# A01_POWER_MCU.net
KiCad netlist of a schematic drawn in Altium Designer
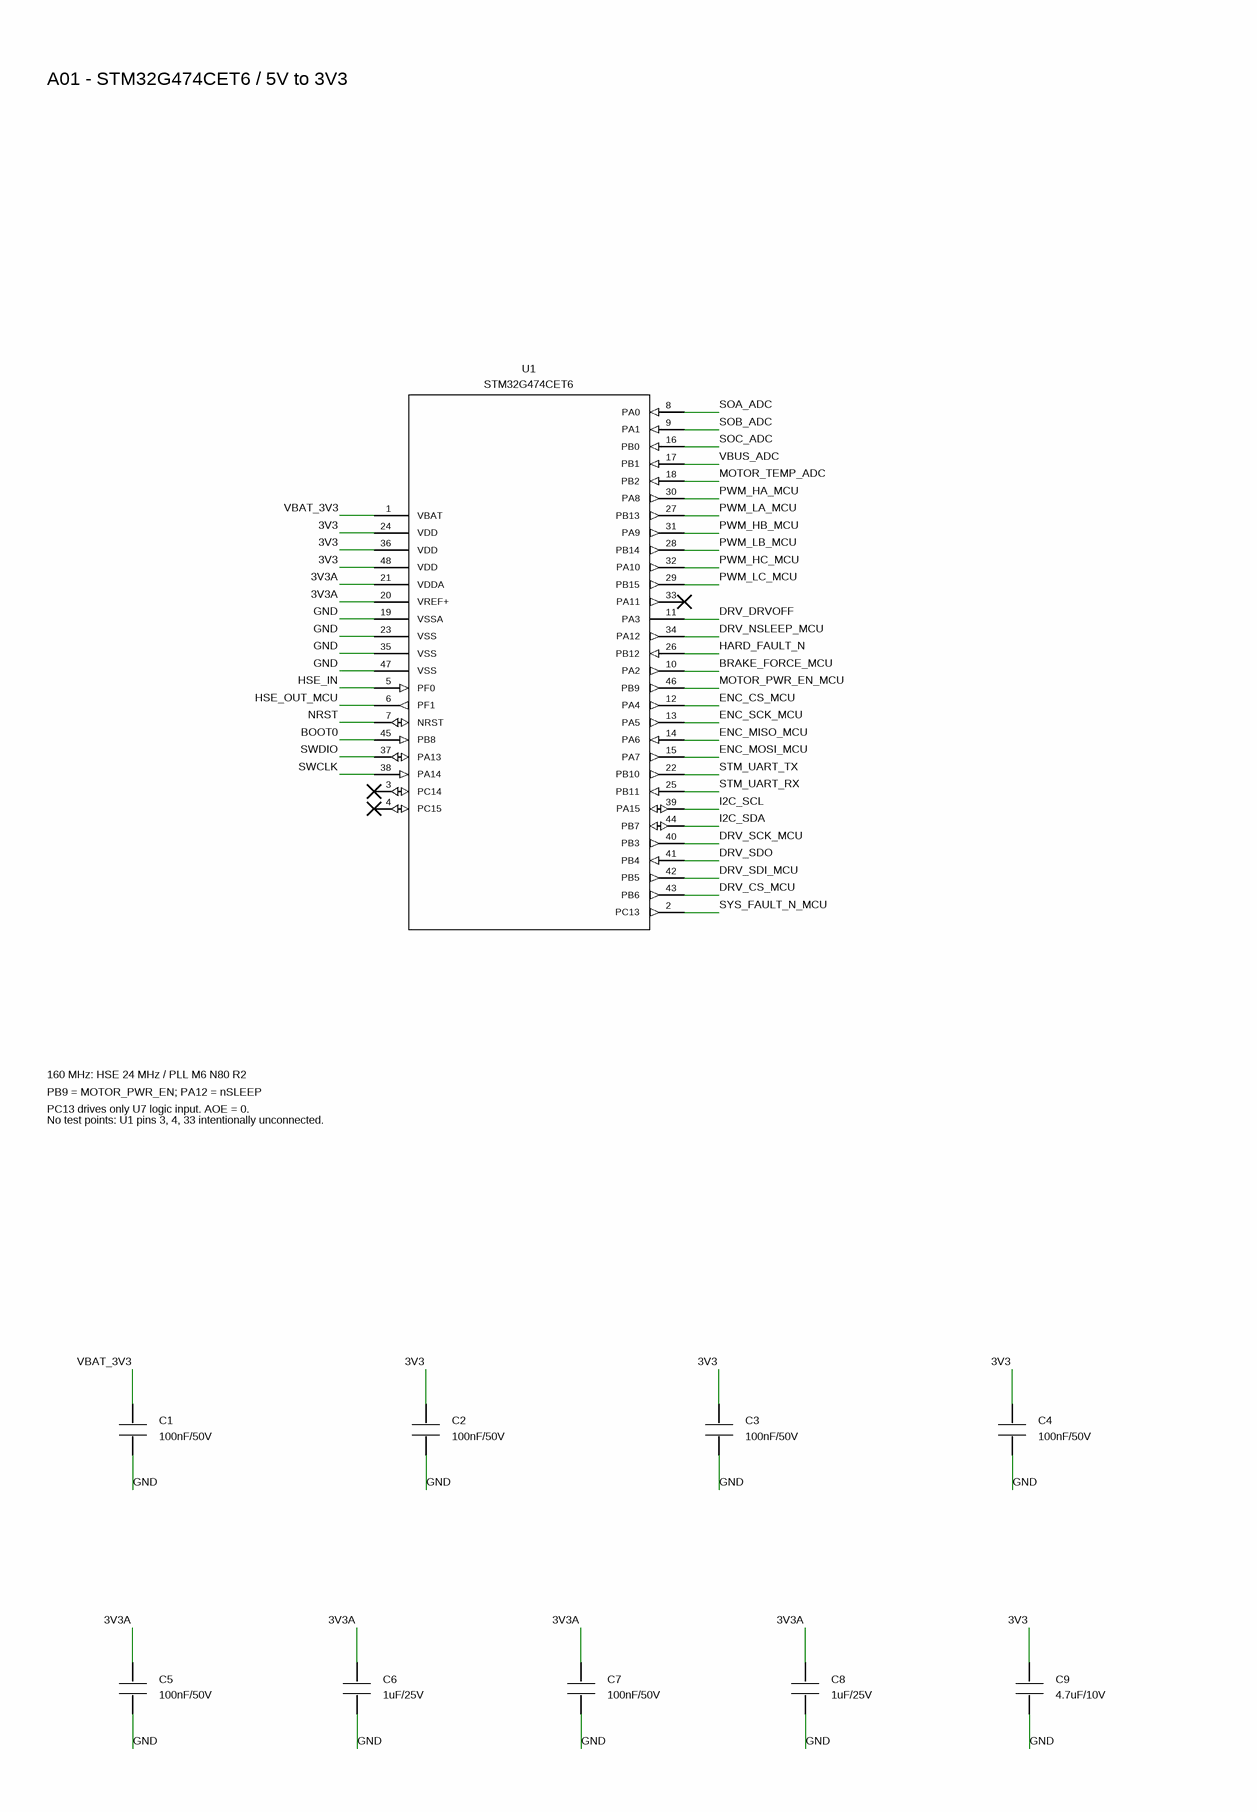
[diagram p0: A01_POWER_MCU.SchDoc, left]
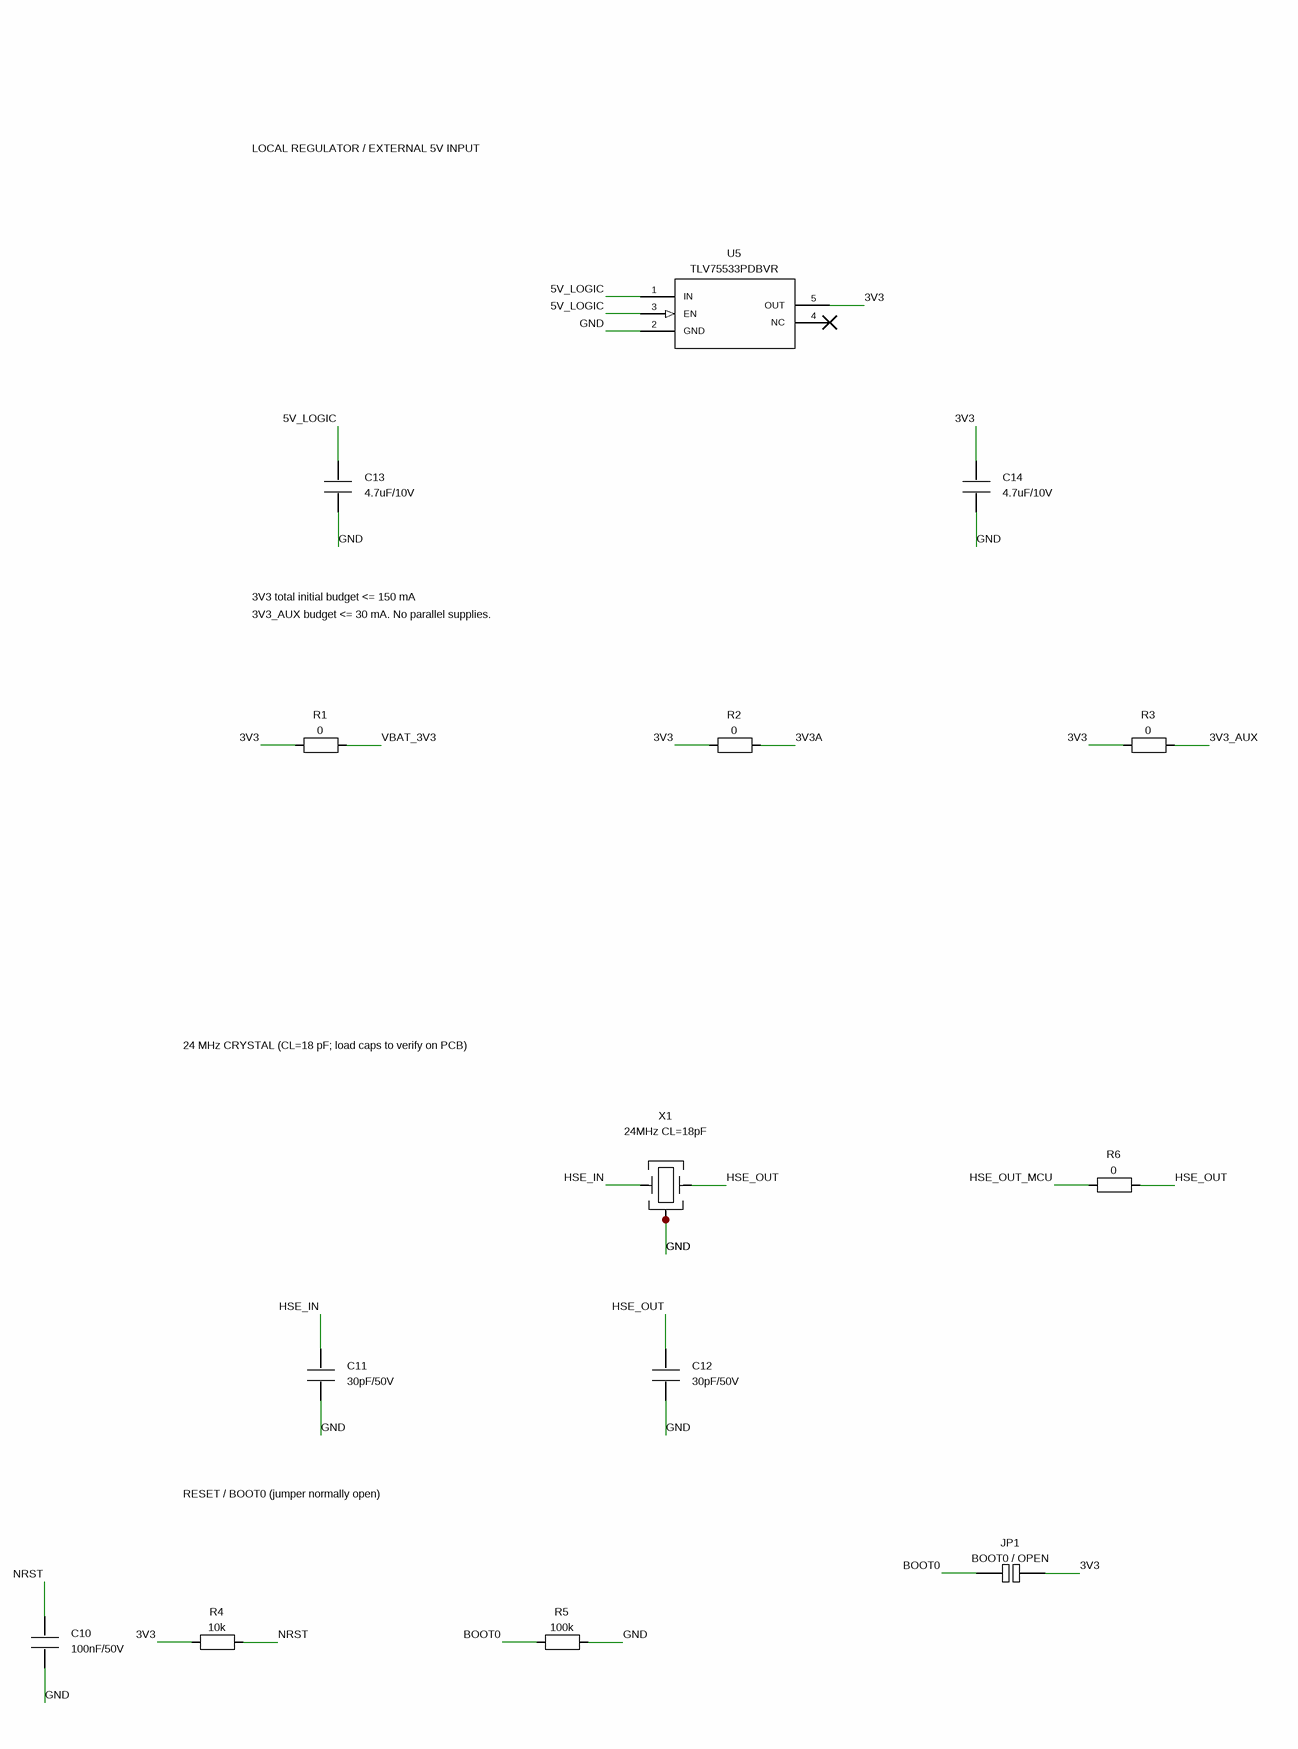
[diagram p1: A01_POWER_MCU.SchDoc, right]

(export (version "E")
  (design (tool "Eeschema 10.0.6"))
  (components
    (comp (ref "C1")
      (value "100nF/50V")
      (footprint "User_STM32F407_Ctrl:C0603_M")
      (description "电容")
      (fields (field (name "MPN") "CL10B104KB8NNNC"))
      (libsource (lib "altium-import") (part "root_0_C_"))
    )
    (comp (ref "C2")
      (value "100nF/50V")
      (footprint "User_STM32F407_Ctrl:C0603_M")
      (description "电容")
      (fields (field (name "MPN") "CL10B104KB8NNNC"))
      (libsource (lib "altium-import") (part "root_0_C_"))
    )
    (comp (ref "C3")
      (value "100nF/50V")
      (footprint "User_STM32F407_Ctrl:C0603_M")
      (description "电容")
      (fields (field (name "MPN") "CL10B104KB8NNNC"))
      (libsource (lib "altium-import") (part "root_0_C_"))
    )
    (comp (ref "C4")
      (value "100nF/50V")
      (footprint "User_STM32F407_Ctrl:C0603_M")
      (description "电容")
      (fields (field (name "MPN") "CL10B104KB8NNNC"))
      (libsource (lib "altium-import") (part "root_0_C_"))
    )
    (comp (ref "C5")
      (value "100nF/50V")
      (footprint "User_STM32F407_Ctrl:C0603_M")
      (description "电容")
      (fields (field (name "MPN") "CL10B104KB8NNNC"))
      (libsource (lib "altium-import") (part "root_0_C_"))
    )
    (comp (ref "C6")
      (value "1uF/25V")
      (footprint "User_STM32F407_Ctrl:C0603_M")
      (description "电容")
      (fields (field (name "MPN") "CL10A105KA8NNNC"))
      (libsource (lib "altium-import") (part "root_0_C_"))
    )
    (comp (ref "C7")
      (value "100nF/50V")
      (footprint "User_STM32F407_Ctrl:C0603_M")
      (description "电容")
      (fields (field (name "MPN") "CL10B104KB8NNNC"))
      (libsource (lib "altium-import") (part "root_0_C_"))
    )
    (comp (ref "C8")
      (value "1uF/25V")
      (footprint "User_STM32F407_Ctrl:C0603_M")
      (description "电容")
      (fields (field (name "MPN") "CL10A105KA8NNNC"))
      (libsource (lib "altium-import") (part "root_0_C_"))
    )
    (comp (ref "C9")
      (value "4.7uF/10V")
      (footprint "User_STM32F407_Ctrl:C0805_M")
      (description "电容")
      (fields (field (name "MPN") "通用 0805 4.7 µF 10 V X7R"))
      (libsource (lib "altium-import") (part "root_0_C_"))
    )
    (comp (ref "C10")
      (value "100nF/50V")
      (footprint "User_STM32F407_Ctrl:C0603_M")
      (description "电容")
      (fields (field (name "MPN") "CL10B104KB8NNNC"))
      (libsource (lib "altium-import") (part "root_0_C_"))
    )
    (comp (ref "C11")
      (value "30pF/50V")
      (footprint "User_STM32F407_Ctrl:C0603_M")
      (description "电容")
      (fields (field (name "MPN") "通用 0603 30 pF 50 V C0G"))
      (libsource (lib "altium-import") (part "root_0_C_"))
    )
    (comp (ref "C12")
      (value "30pF/50V")
      (footprint "User_STM32F407_Ctrl:C0603_M")
      (description "电容")
      (fields (field (name "MPN") "通用 0603 30 pF 50 V C0G"))
      (libsource (lib "altium-import") (part "root_0_C_"))
    )
    (comp (ref "C13")
      (value "4.7uF/10V")
      (footprint "User_STM32F407_Ctrl:C0805_M")
      (description "电容")
      (fields (field (name "MPN") "通用 0805 4.7 µF 10 V X7R"))
      (libsource (lib "altium-import") (part "root_0_C_"))
    )
    (comp (ref "C14")
      (value "4.7uF/10V")
      (footprint "User_STM32F407_Ctrl:C0805_M")
      (description "电容")
      (fields (field (name "MPN") "通用 0805 4.7 µF 10 V X7R"))
      (libsource (lib "altium-import") (part "root_0_C_"))
    )
    (comp (ref "JP1")
      (value "BOOT0 / OPEN")
      (description "BOOT焊桥")
      (fields (field (name "MPN") "PCB焊盘，无采购"))
      (libsource (lib "altium-import") (part "root_0_SolderJumper_2_Open_"))
    )
    (comp (ref "R1")
      (value "0")
      (footprint "User_STM32F407_Ctrl:R0603_M")
      (description "电阻")
      (fields (field (name "MPN") "通用0Ω跳线 0.1 W"))
      (libsource (lib "altium-import") (part "root_1_R_"))
    )
    (comp (ref "R2")
      (value "0")
      (footprint "User_STM32F407_Ctrl:R0805_M")
      (description "电阻")
      (fields (field (name "MPN") "通用0Ω跳线 0.125 W"))
      (libsource (lib "altium-import") (part "root_1_R_"))
    )
    (comp (ref "R3")
      (value "0")
      (footprint "User_STM32F407_Ctrl:R0603_M")
      (description "电阻")
      (fields (field (name "MPN") "通用0Ω跳线 0.1 W"))
      (libsource (lib "altium-import") (part "root_1_R_"))
    )
    (comp (ref "R4")
      (value "10k")
      (footprint "User_STM32F407_Ctrl:R0603_M")
      (description "电阻")
      (fields (field (name "MPN") "通用厚膜 10k 1% 0.1 W"))
      (libsource (lib "altium-import") (part "root_1_R_"))
    )
    (comp (ref "R5")
      (value "100k")
      (footprint "User_STM32F407_Ctrl:R0603_M")
      (description "电阻")
      (fields (field (name "MPN") "通用厚膜 100k 1% 0.1 W"))
      (libsource (lib "altium-import") (part "root_1_R_"))
    )
    (comp (ref "R6")
      (value "0")
      (footprint "User_STM32F407_Ctrl:R0603_M")
      (description "电阻")
      (fields (field (name "MPN") "通用0Ω跳线 0.1 W"))
      (libsource (lib "altium-import") (part "root_1_R_"))
    )
    (comp (ref "U1")
      (value "STM32G474CET6")
      (footprint "User_SamacSys:QFP50P900X900X160-48N")
      (description "FOC主控")
      (libsource (lib "altium-import") (part "root_0_STM32G474CET6_"))
    )
    (comp (ref "U5")
      (value "TLV75533PDBVR")
      (footprint "User_SamacSys:SOT95P280X145-5N")
      (description "本地3.3 V稳压")
      (libsource (lib "altium-import") (part "root_0_TLV75533PDBVR_"))
    )
    (comp (ref "X1")
      (value "24MHz CL=18pF")
      (footprint "User_STM32F407_Ctrl:XTAL-3225-4P")
      (description "无源晶体")
      (fields (field (name "MPN") "ABM8-24.000MHZ-B2-T"))
      (libsource (lib "altium-import") (part "root_0_Crystal_GND24_"))
    )
  )
  (nets
    (net (code "1") (name "/3V3") (class "Default")
      (node (ref "C14") (pin "1") (pintype "passive"))
      (node (ref "C2") (pin "1") (pintype "passive"))
      (node (ref "C3") (pin "1") (pintype "passive"))
      (node (ref "C4") (pin "1") (pintype "passive"))
      (node (ref "C9") (pin "1") (pintype "passive"))
      (node (ref "JP1") (pin "2") (pinfunction "2_2") (pintype "passive"))
      (node (ref "R1") (pin "1") (pintype "passive"))
      (node (ref "R2") (pin "1") (pintype "passive"))
      (node (ref "R3") (pin "1") (pintype "passive"))
      (node (ref "R4") (pin "1") (pintype "passive"))
      (node (ref "U1") (pin "24") (pinfunction "VDD_24") (pintype "power_in"))
      (node (ref "U1") (pin "36") (pinfunction "VDD_36") (pintype "power_in"))
      (node (ref "U1") (pin "48") (pinfunction "VDD_48") (pintype "power_in"))
      (node (ref "U5") (pin "5") (pinfunction "OUT_5") (pintype "power_in"))
    )
    (net (code "2") (name "/3V3A") (class "Default")
      (node (ref "C5") (pin "1") (pintype "passive"))
      (node (ref "C6") (pin "1") (pintype "passive"))
      (node (ref "C7") (pin "1") (pintype "passive"))
      (node (ref "C8") (pin "1") (pintype "passive"))
      (node (ref "R2") (pin "2") (pintype "passive"))
      (node (ref "U1") (pin "20") (pinfunction "VREF+_20") (pintype "power_in"))
      (node (ref "U1") (pin "21") (pinfunction "VDDA_21") (pintype "power_in"))
    )
    (net (code "3") (name "/3V3_AUX") (class "Default") (node (ref "R3") (pin "2") (pintype "passive")))
    (net (code "4") (name "/5V_LOGIC") (class "Default")
      (node (ref "C13") (pin "1") (pintype "passive"))
      (node (ref "U5") (pin "1") (pinfunction "IN_1") (pintype "power_in"))
      (node (ref "U5") (pin "3") (pinfunction "EN_3") (pintype "input"))
    )
    (net (code "5") (name "/BOOT0") (class "Default")
      (node (ref "JP1") (pin "1") (pinfunction "1_1") (pintype "passive"))
      (node (ref "R5") (pin "1") (pintype "passive"))
      (node (ref "U1") (pin "45") (pinfunction "PB8_45") (pintype "input"))
    )
    (net (code "6") (name "/BRAKE_FORCE_MCU") (class "Default")
      (node (ref "U1") (pin "10") (pinfunction "PA2_10") (pintype "output"))
    )
    (net (code "7") (name "/DRV_CS_MCU") (class "Default")
      (node (ref "U1") (pin "43") (pinfunction "PB6_43") (pintype "output"))
    )
    (net (code "8") (name "/DRV_DRVOFF") (class "Default")
      (node (ref "U1") (pin "11") (pinfunction "PA3_11") (pintype "open_collector"))
    )
    (net (code "9") (name "/DRV_NSLEEP_MCU") (class "Default")
      (node (ref "U1") (pin "34") (pinfunction "PA12_34") (pintype "output"))
    )
    (net (code "10") (name "/DRV_SCK_MCU") (class "Default")
      (node (ref "U1") (pin "40") (pinfunction "PB3_40") (pintype "output"))
    )
    (net (code "11") (name "/DRV_SDI_MCU") (class "Default")
      (node (ref "U1") (pin "42") (pinfunction "PB5_42") (pintype "output"))
    )
    (net (code "12") (name "/DRV_SDO") (class "Default")
      (node (ref "U1") (pin "41") (pinfunction "PB4_41") (pintype "input"))
    )
    (net (code "13") (name "/ENC_CS_MCU") (class "Default")
      (node (ref "U1") (pin "12") (pinfunction "PA4_12") (pintype "output"))
    )
    (net (code "14") (name "/ENC_MISO_MCU") (class "Default")
      (node (ref "U1") (pin "14") (pinfunction "PA6_14") (pintype "input"))
    )
    (net (code "15") (name "/ENC_MOSI_MCU") (class "Default")
      (node (ref "U1") (pin "15") (pinfunction "PA7_15") (pintype "output"))
    )
    (net (code "16") (name "/ENC_SCK_MCU") (class "Default")
      (node (ref "U1") (pin "13") (pinfunction "PA5_13") (pintype "output"))
    )
    (net (code "17") (name "/GND") (class "Default")
      (node (ref "C1") (pin "2") (pintype "passive"))
      (node (ref "C10") (pin "2") (pintype "passive"))
      (node (ref "C11") (pin "2") (pintype "passive"))
      (node (ref "C12") (pin "2") (pintype "passive"))
      (node (ref "C13") (pin "2") (pintype "passive"))
      (node (ref "C14") (pin "2") (pintype "passive"))
      (node (ref "C2") (pin "2") (pintype "passive"))
      (node (ref "C3") (pin "2") (pintype "passive"))
      (node (ref "C4") (pin "2") (pintype "passive"))
      (node (ref "C5") (pin "2") (pintype "passive"))
      (node (ref "C6") (pin "2") (pintype "passive"))
      (node (ref "C7") (pin "2") (pintype "passive"))
      (node (ref "C8") (pin "2") (pintype "passive"))
      (node (ref "C9") (pin "2") (pintype "passive"))
      (node (ref "R5") (pin "2") (pintype "passive"))
      (node (ref "U1") (pin "19") (pinfunction "VSSA_19") (pintype "power_in"))
      (node (ref "U1") (pin "23") (pinfunction "VSS_23") (pintype "power_in"))
      (node (ref "U1") (pin "35") (pinfunction "VSS_35") (pintype "power_in"))
      (node (ref "U1") (pin "47") (pinfunction "VSS_47") (pintype "power_in"))
      (node (ref "U5") (pin "2") (pinfunction "GND_2") (pintype "power_in"))
      (node (ref "X1") (pin "2") (pinfunction "G_2") (pintype "passive"))
      (node (ref "X1") (pin "4") (pinfunction "G_4") (pintype "passive"))
    )
    (net (code "18") (name "/HARD_FAULT_N") (class "Default")
      (node (ref "U1") (pin "26") (pinfunction "PB12_26") (pintype "input"))
    )
    (net (code "19") (name "/HSE_IN") (class "Default")
      (node (ref "C11") (pin "1") (pintype "passive"))
      (node (ref "U1") (pin "5") (pinfunction "PF0_5") (pintype "input"))
      (node (ref "X1") (pin "1") (pinfunction "1_1") (pintype "passive"))
    )
    (net (code "20") (name "/HSE_OUT") (class "Default")
      (node (ref "C12") (pin "1") (pintype "passive"))
      (node (ref "R6") (pin "2") (pintype "passive"))
      (node (ref "X1") (pin "3") (pinfunction "3_3") (pintype "passive"))
    )
    (net (code "21") (name "/HSE_OUT_MCU") (class "Default")
      (node (ref "R6") (pin "1") (pintype "passive"))
      (node (ref "U1") (pin "6") (pinfunction "PF1_6") (pintype "output"))
    )
    (net (code "22") (name "/I2C_SCL") (class "Default")
      (node (ref "U1") (pin "39") (pinfunction "PA15_39") (pintype "bidirectional"))
    )
    (net (code "23") (name "/I2C_SDA") (class "Default")
      (node (ref "U1") (pin "44") (pinfunction "PB7_44") (pintype "bidirectional"))
    )
    (net (code "24") (name "/MOTOR_PWR_EN_MCU") (class "Default")
      (node (ref "U1") (pin "46") (pinfunction "PB9_46") (pintype "output"))
    )
    (net (code "25") (name "/MOTOR_TEMP_ADC") (class "Default")
      (node (ref "U1") (pin "18") (pinfunction "PB2_18") (pintype "input"))
    )
    (net (code "26") (name "/NRST") (class "Default")
      (node (ref "C10") (pin "1") (pintype "passive"))
      (node (ref "R4") (pin "2") (pintype "passive"))
      (node (ref "U1") (pin "7") (pinfunction "NRST_7") (pintype "bidirectional"))
    )
    (net (code "27") (name "/PWM_HA_MCU") (class "Default")
      (node (ref "U1") (pin "30") (pinfunction "PA8_30") (pintype "output"))
    )
    (net (code "28") (name "/PWM_HB_MCU") (class "Default")
      (node (ref "U1") (pin "31") (pinfunction "PA9_31") (pintype "output"))
    )
    (net (code "29") (name "/PWM_HC_MCU") (class "Default")
      (node (ref "U1") (pin "32") (pinfunction "PA10_32") (pintype "output"))
    )
    (net (code "30") (name "/PWM_LA_MCU") (class "Default")
      (node (ref "U1") (pin "27") (pinfunction "PB13_27") (pintype "output"))
    )
    (net (code "31") (name "/PWM_LB_MCU") (class "Default")
      (node (ref "U1") (pin "28") (pinfunction "PB14_28") (pintype "output"))
    )
    (net (code "32") (name "/PWM_LC_MCU") (class "Default")
      (node (ref "U1") (pin "29") (pinfunction "PB15_29") (pintype "output"))
    )
    (net (code "33") (name "/SOA_ADC") (class "Default")
      (node (ref "U1") (pin "8") (pinfunction "PA0_8") (pintype "input"))
    )
    (net (code "34") (name "/SOB_ADC") (class "Default")
      (node (ref "U1") (pin "9") (pinfunction "PA1_9") (pintype "input"))
    )
    (net (code "35") (name "/SOC_ADC") (class "Default")
      (node (ref "U1") (pin "16") (pinfunction "PB0_16") (pintype "input"))
    )
    (net (code "36") (name "/STM_UART_RX") (class "Default")
      (node (ref "U1") (pin "25") (pinfunction "PB11_25") (pintype "input"))
    )
    (net (code "37") (name "/STM_UART_TX") (class "Default")
      (node (ref "U1") (pin "22") (pinfunction "PB10_22") (pintype "output"))
    )
    (net (code "38") (name "/SWCLK") (class "Default")
      (node (ref "U1") (pin "38") (pinfunction "PA14_38") (pintype "input"))
    )
    (net (code "39") (name "/SWDIO") (class "Default")
      (node (ref "U1") (pin "37") (pinfunction "PA13_37") (pintype "bidirectional"))
    )
    (net (code "40") (name "/SYS_FAULT_N_MCU") (class "Default")
      (node (ref "U1") (pin "2") (pinfunction "PC13_2") (pintype "output"))
    )
    (net (code "41") (name "/VBAT_3V3") (class "Default")
      (node (ref "C1") (pin "1") (pintype "passive"))
      (node (ref "R1") (pin "2") (pintype "passive"))
      (node (ref "U1") (pin "1") (pinfunction "VBAT_1") (pintype "power_in"))
    )
    (net (code "42") (name "/VBUS_ADC") (class "Default")
      (node (ref "U1") (pin "17") (pinfunction "PB1_17") (pintype "input"))
    )
    (net (code "43") (name "unconnected-(U1-PA11-Pad33)") (class "Default")
      (node (ref "U1") (pin "33") (pinfunction "PA11_33") (pintype "output+no_connect"))
    )
    (net (code "44") (name "unconnected-(U1-PC14-Pad3)") (class "Default")
      (node (ref "U1") (pin "3") (pinfunction "PC14_3") (pintype "bidirectional+no_connect"))
    )
    (net (code "45") (name "unconnected-(U1-PC15-Pad4)") (class "Default")
      (node (ref "U1") (pin "4") (pinfunction "PC15_4") (pintype "bidirectional+no_connect"))
    )
    (net (code "46") (name "unconnected-(U5-NC-Pad4)") (class "Default")
      (node (ref "U5") (pin "4") (pinfunction "NC_4") (pintype "passive+no_connect"))
    )
  )
)
